# PeltierDrive.net
KiCad netlist of a schematic drawn in Altium Designer
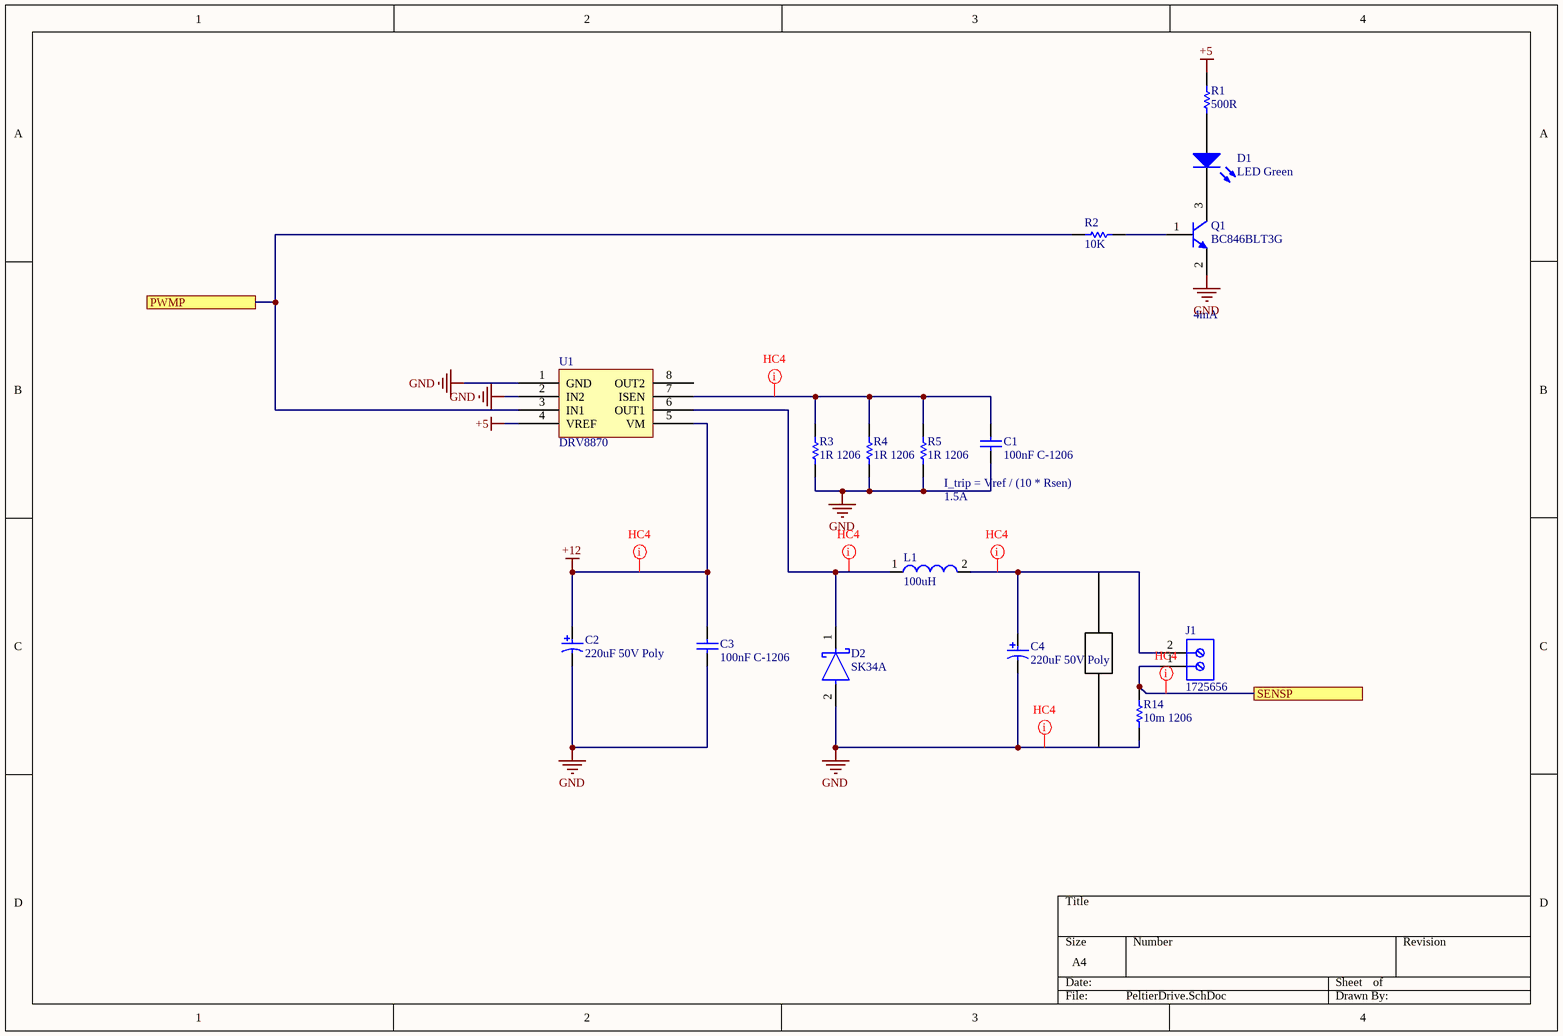
[diagram p0: PeltierDrive.SchDoc]

(export (version "E")
  (design (tool "Eeschema 10.0.6"))
  (components
    (comp (ref "C1")
      (value "100nF C-1206")
      (footprint "C-1206")
      (description "Ceramic 50V 1206")
      (fields (field (name "TOLERANCE") "Â±20%"))
      (libsource (lib "Schlib1") (part "C-1206"))
    )
    (comp (ref "C2")
      (value "220uF 50V Poly")
      (footprint "CAPAE127P600-8N")
      (fields (field (name "VOLTAGE") "25VDC") (field (name "MANUFACTURER") "AVX"))
      (libsource (lib "Schlib1") (part "C-Poly"))
    )
    (comp (ref "C3")
      (value "100nF C-1206")
      (footprint "C-1206")
      (description "Ceramic 50V 1206")
      (fields (field (name "TOLERANCE") "Â±20%"))
      (libsource (lib "Schlib1") (part "C-1206"))
    )
    (comp (ref "C4")
      (value "220uF 50V Poly")
      (footprint "CAPAE127P600-8N")
      (fields (field (name "VOLTAGE") "25VDC") (field (name "MANUFACTURER") "AVX"))
      (libsource (lib "Schlib1") (part "C-Poly"))
    )
    (comp (ref "D1")
      (value "LED Green")
      (footprint "0603_A")
      (description "SMD mono-color Chip LED, WL-SMCW, Green")
      (fields (field (name "PARTNUMBER") "150060GS75000") (field (name "MANUFACTURER") "Wuerth Elektronik"))
      (libsource (lib "Altium Content Vault") (part "WE-LED_K1A2-2"))
    )
    (comp (ref "D2")
      (value "SK34A")
      (footprint "FP-DO-214AC-MFG")
      (description "DIODE SCHOTTKY 5A 30V SMA")
      (libsource (lib "Altium Content Vault") (part "1d6ec82d83fb6aee721767c19dac4b9"))
    )
    (comp (ref "J1")
      (value "1725656")
      (footprint "PHOE-1725656-2")
      (description "Male Header, Pitch 2.54 mm, 1 x 2 Position, Height 9 mm, Tail Length 3.5 mm")
      (fields (field (name "MANUFACTURER") "Phoenix Contact"))
      (libsource (lib "Altium Content Vault") (part "CN-1P-F-TB2"))
    )
    (comp (ref "L1")
      (value "100uH")
      (footprint "INDC177172X70N")
      (description "PA4344.104NLT\r\nhttps://products.pulseelex.com/files/product_files/P771.pdf")
      (fields (field (name "MANUFACTURER") "Wuerth Elektronik") (field (name "PARTNUMBER") "74479763215"))
      (libsource (lib "Schlib1") (part "Inductor1717"))
    )
    (comp (ref "Q1")
      (value "BC846BLT3G")
      (footprint "ONSC-SOT-23-3-318-08_V")
      (description "General Purpose Transistor, NPN Silicon, 3-Pin SOT-23, Pb-Free, Tape and Reel")
      (fields (field (name "MANUFACTURER") "On Semiconductor"))
      (libsource (lib "Altium Content Vault") (part "ONSC-NPN-B1E2C3-3"))
    )
    (comp (ref "R1")
      (value "500R")
      (footprint "RESC0603(1608)_L")
      (description "510R 0.1W 5% 0603 (1608 Metric)  SMD")
      (fields (field (name "POWER") "0.1 W") (field (name "TOLERANCE") "5 %"))
      (libsource (lib "Altium Content Vault") (part "RES"))
    )
    (comp (ref "R2")
      (value "10K")
      (footprint "RESC0603(1608)_N")
      (description "10K 0.1W 1% 0603 (1608 Metric)  SMD")
      (fields (field (name "POWER") "0.1 W") (field (name "TOLERANCE") "1 %"))
      (libsource (lib "Altium Content Vault") (part "RES"))
    )
    (comp (ref "R3")
      (value "1R 1206")
      (footprint "RESC1206(3216)_N")
      (description "1R2 0.25W 5% 1206 (3216 Metric)  SMD")
      (fields (field (name "POWER") "0.25 W") (field (name "TOLERANCE") "5 %"))
      (libsource (lib "Altium Content Vault") (part "RES"))
    )
    (comp (ref "R4")
      (value "1R 1206")
      (footprint "RESC1206(3216)_N")
      (description "1R2 0.25W 5% 1206 (3216 Metric)  SMD")
      (fields (field (name "POWER") "0.25 W") (field (name "TOLERANCE") "5 %"))
      (libsource (lib "Altium Content Vault") (part "RES"))
    )
    (comp (ref "R5")
      (value "1R 1206")
      (footprint "RESC1206(3216)_N")
      (description "1R2 0.25W 5% 1206 (3216 Metric)  SMD")
      (fields (field (name "POWER") "0.25 W") (field (name "TOLERANCE") "5 %"))
      (libsource (lib "Altium Content Vault") (part "RES"))
    )
    (comp (ref "R14")
      (value "10m 1206")
      (footprint "RESC1206(3216)_N")
      (description "1R2 0.25W 5% 1206 (3216 Metric)  SMD")
      (fields (field (name "POWER") "0.25 W") (field (name "TOLERANCE") "5 %"))
      (libsource (lib "Altium Content Vault") (part "RES"))
    )
    (comp (ref "U1")
      (value "DRV8870")
      (footprint "SOIC127P600X170_HS-9N")
      (libsource (lib "Schlib1") (part "DRV8870"))
    )
  )
  (nets
    (net (code "1") (name "+5") (class "Default")
      (node (ref "R1") (pin "2") (pinfunction "2_2") (pintype "passive"))
      (node (ref "U1") (pin "4") (pinfunction "VREF_4") (pintype "passive"))
    )
    (net (code "2") (name "+12") (class "Default")
      (node (ref "C2") (pin "1") (pinfunction "1_1") (pintype "passive"))
      (node (ref "C3") (pin "2") (pinfunction "2_2") (pintype "passive"))
      (node (ref "U1") (pin "5") (pinfunction "VM_5") (pintype "passive"))
    )
    (net (code "3") (name "/PWMP") (class "Default")
      (node (ref "R2") (pin "1") (pinfunction "1_1") (pintype "passive"))
      (node (ref "U1") (pin "3") (pinfunction "IN1_3") (pintype "passive"))
    )
    (net (code "4") (name "/SENSP") (class "Default")
      (node (ref "J1") (pin "1") (pinfunction "1_1") (pintype "passive"))
      (node (ref "R14") (pin "2") (pinfunction "2_2") (pintype "passive"))
    )
    (net (code "5") (name "GND") (class "Default")
      (node (ref "C1") (pin "1") (pinfunction "1_1") (pintype "passive"))
      (node (ref "C2") (pin "2") (pinfunction "2_2") (pintype "passive"))
      (node (ref "C3") (pin "1") (pinfunction "1_1") (pintype "passive"))
      (node (ref "C4") (pin "2") (pinfunction "2_2") (pintype "passive"))
      (node (ref "D2") (pin "2") (pinfunction "A_2") (pintype "passive"))
      (node (ref "Q1") (pin "2") (pinfunction "E_2") (pintype "passive"))
      (node (ref "R14") (pin "1") (pinfunction "1_1") (pintype "passive"))
      (node (ref "R3") (pin "1") (pinfunction "1_1") (pintype "passive"))
      (node (ref "R4") (pin "1") (pinfunction "1_1") (pintype "passive"))
      (node (ref "R5") (pin "1") (pinfunction "1_1") (pintype "passive"))
      (node (ref "U1") (pin "1") (pinfunction "GND_1") (pintype "passive"))
      (node (ref "U1") (pin "2") (pinfunction "IN2_2") (pintype "passive"))
    )
    (net (code "6") (name "Net-(C4-Pad1)") (class "Default")
      (node (ref "C4") (pin "1") (pinfunction "1_1") (pintype "passive"))
      (node (ref "J1") (pin "2") (pinfunction "2_2") (pintype "passive"))
      (node (ref "L1") (pin "2") (pinfunction "2_2") (pintype "passive"))
    )
    (net (code "7") (name "Net-(D1-A)") (class "Default")
      (node (ref "D1") (pin "2") (pinfunction "A_2") (pintype "passive"))
      (node (ref "R1") (pin "1") (pinfunction "1_1") (pintype "passive"))
    )
    (net (code "8") (name "Net-(D1-K)") (class "Default")
      (node (ref "D1") (pin "1") (pinfunction "K_1") (pintype "passive"))
      (node (ref "Q1") (pin "3") (pinfunction "C_3") (pintype "passive"))
    )
    (net (code "9") (name "Net-(D2-C)") (class "Default")
      (node (ref "D2") (pin "1") (pinfunction "C_1") (pintype "passive"))
      (node (ref "L1") (pin "1") (pinfunction "1_1") (pintype "passive"))
      (node (ref "U1") (pin "6") (pinfunction "OUT1_6") (pintype "passive"))
    )
    (net (code "10") (name "Net-(Q1-B)") (class "Default")
      (node (ref "Q1") (pin "1") (pinfunction "B_1") (pintype "passive"))
      (node (ref "R2") (pin "2") (pinfunction "2_2") (pintype "passive"))
    )
    (net (code "11") (name "Net-(U1-ISEN)") (class "Default")
      (node (ref "C1") (pin "2") (pinfunction "2_2") (pintype "passive"))
      (node (ref "R3") (pin "2") (pinfunction "2_2") (pintype "passive"))
      (node (ref "R4") (pin "2") (pinfunction "2_2") (pintype "passive"))
      (node (ref "R5") (pin "2") (pinfunction "2_2") (pintype "passive"))
      (node (ref "U1") (pin "7") (pinfunction "ISEN_7") (pintype "passive"))
    )
    (net (code "12") (name "unconnected-(U1-OUT2-Pad8)") (class "Default")
      (node (ref "U1") (pin "8") (pinfunction "OUT2_8") (pintype "passive"))
    )
  )
)
